# EtchController.net
KiCad netlist of a schematic drawn in EAGLE
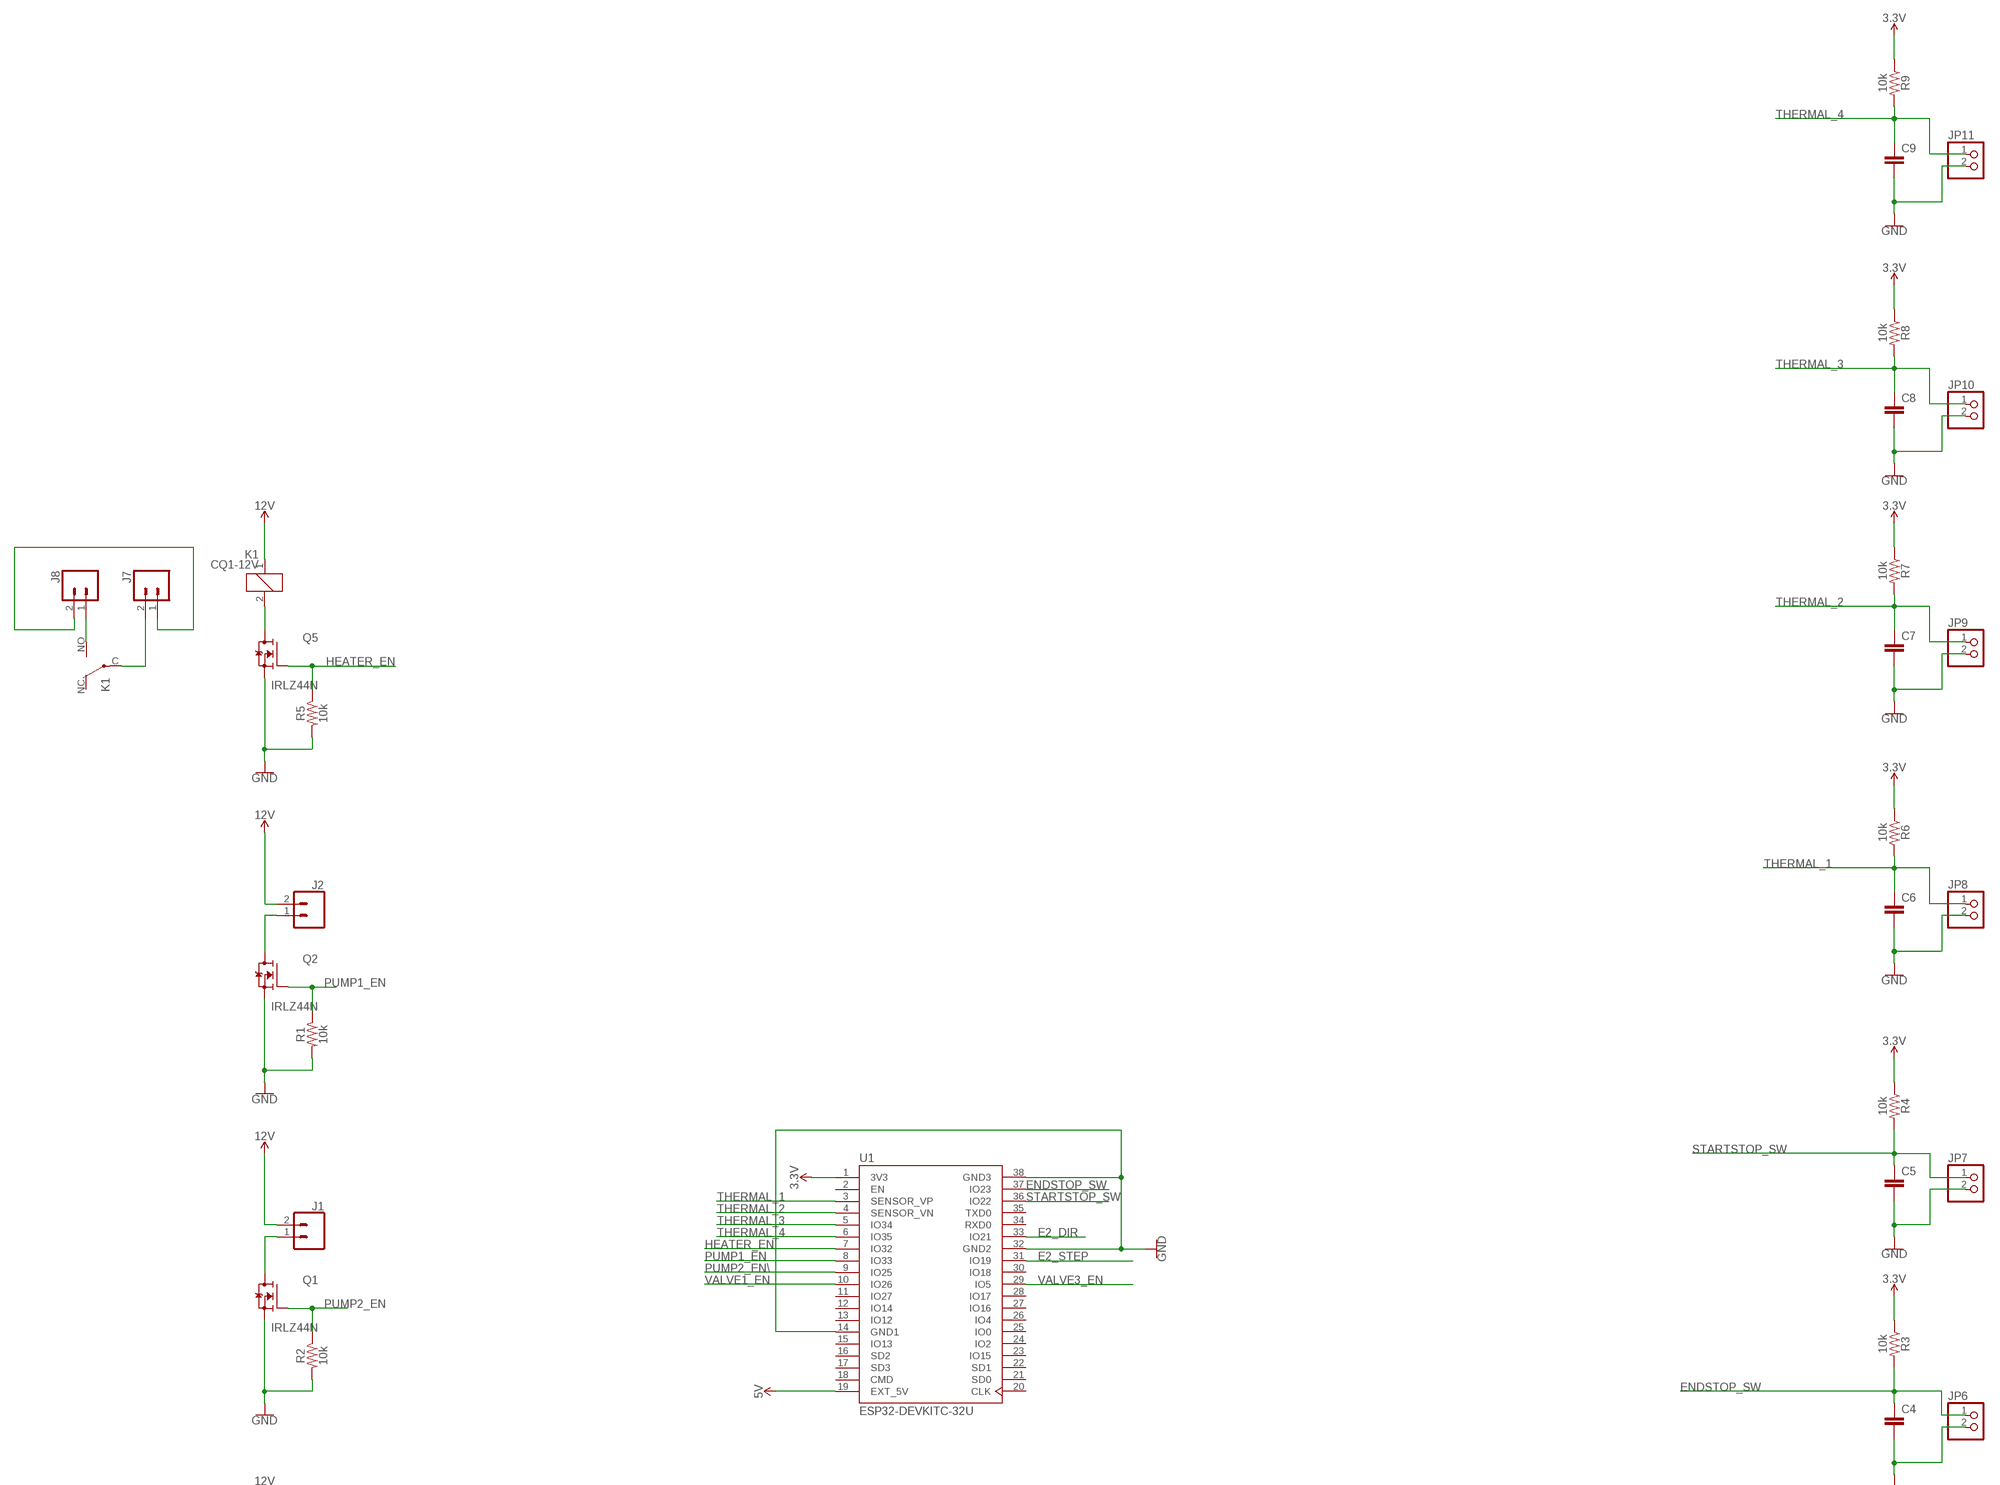
[diagram p0: schematic, sheet 1, part 1 of 2]
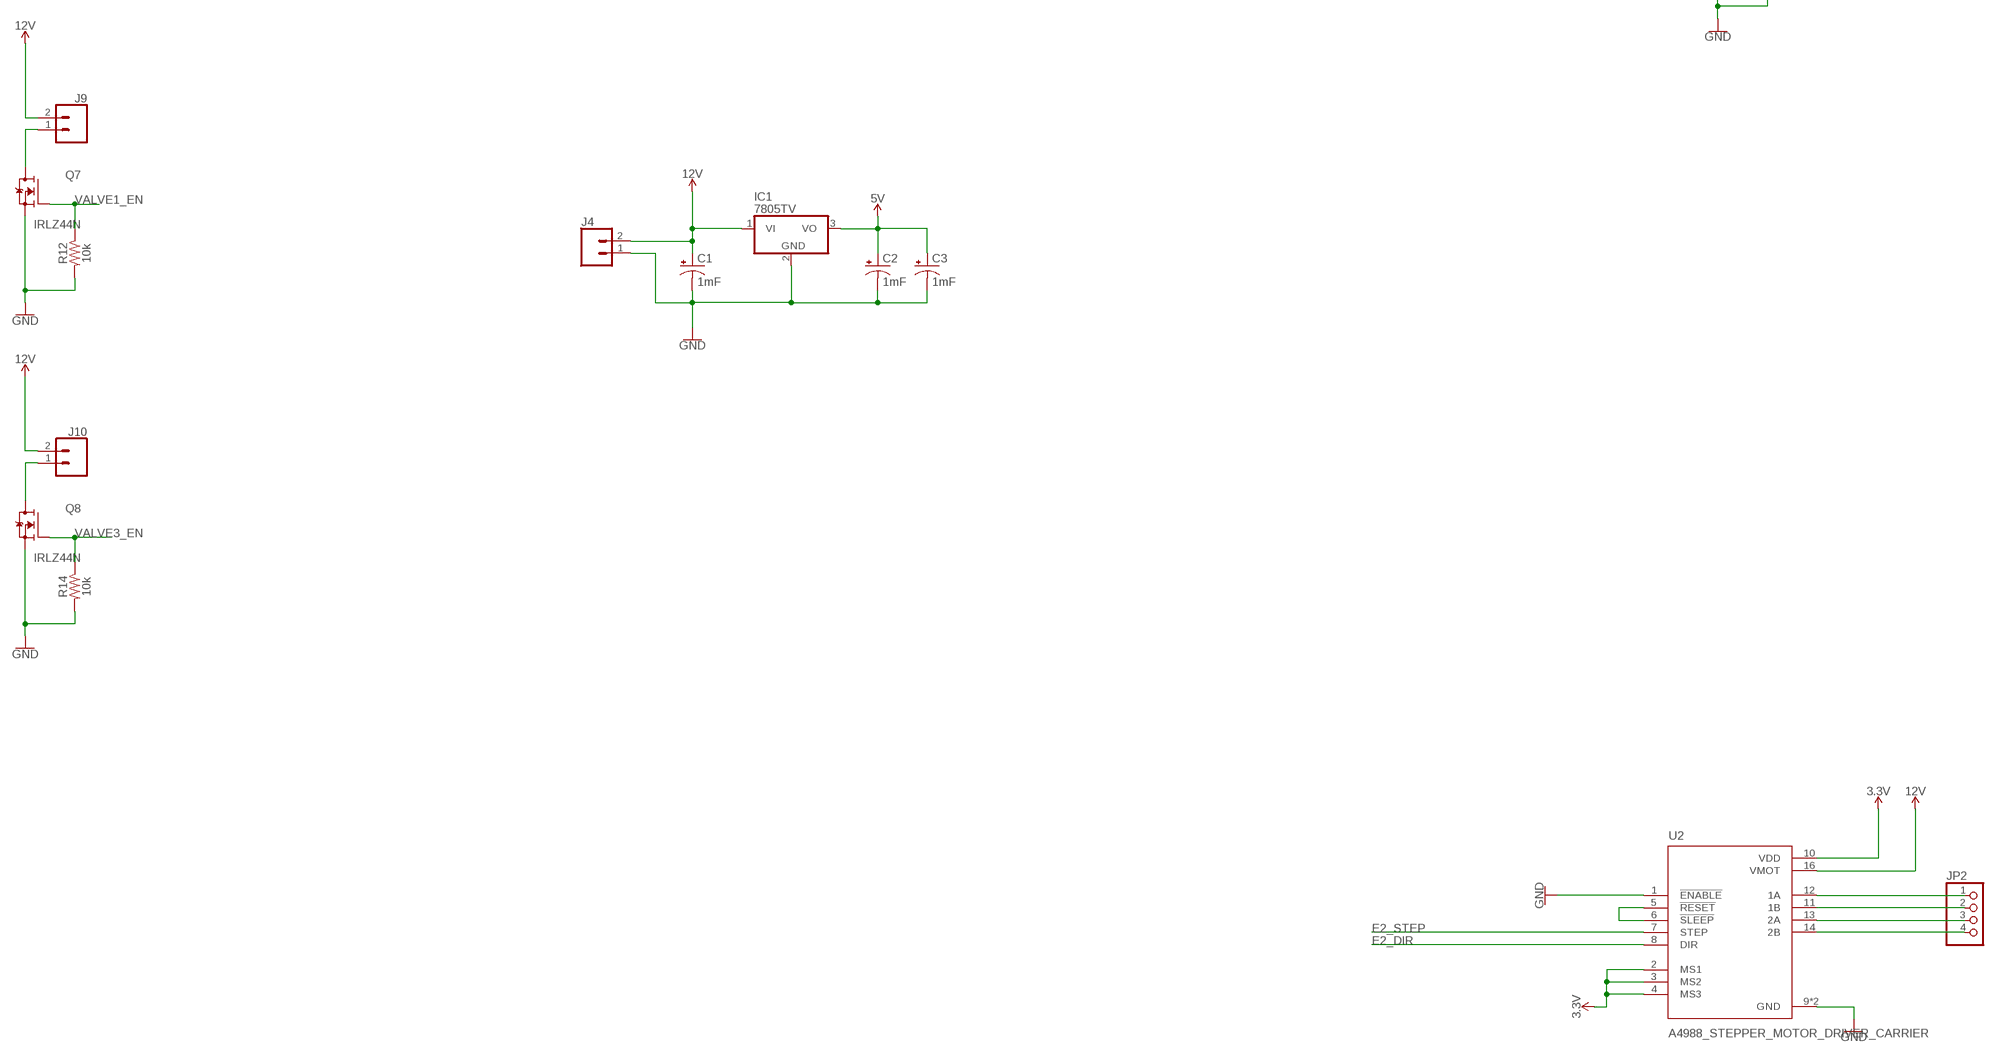
[diagram p1: schematic, sheet 1, part 2 of 2]

(export (version "E")
  (design (tool "Eeschema 10.0.6"))
  (components
    (comp (ref "C1")
      (value "1mF")
      (footprint "eagle-import:CPOL-RADIAL-5MM-10MM")
      (libsource (lib "eagle-import") (part "1000UF-RADIAL-5MM-25V-20%"))
    )
    (comp (ref "C2")
      (value "1mF")
      (footprint "eagle-import:CPOL-RADIAL-5MM-10MM")
      (libsource (lib "eagle-import") (part "1000UF-RADIAL-5MM-25V-20%"))
    )
    (comp (ref "C3")
      (value "1mF")
      (footprint "eagle-import:CPOL-RADIAL-5MM-10MM")
      (libsource (lib "eagle-import") (part "1000UF-RADIAL-5MM-25V-20%"))
    )
    (comp (ref "C4")
      (value "C2,5-3")
      (footprint "eagle-import:C2.5-3")
      (libsource (lib "eagle-import") (part "C2,5-3"))
    )
    (comp (ref "C5")
      (value "C2,5-3")
      (footprint "eagle-import:C2.5-3")
      (libsource (lib "eagle-import") (part "C2,5-3"))
    )
    (comp (ref "C6")
      (value "C2,5-3")
      (footprint "eagle-import:C2.5-3")
      (libsource (lib "eagle-import") (part "C2,5-3"))
    )
    (comp (ref "C7")
      (value "C2,5-3")
      (footprint "eagle-import:C2.5-3")
      (libsource (lib "eagle-import") (part "C2,5-3"))
    )
    (comp (ref "C8")
      (value "C2,5-3")
      (footprint "eagle-import:C2.5-3")
      (libsource (lib "eagle-import") (part "C2,5-3"))
    )
    (comp (ref "C9")
      (value "C2,5-3")
      (footprint "eagle-import:C2.5-3")
      (libsource (lib "eagle-import") (part "C2,5-3"))
    )
    (comp (ref "IC1")
      (value "7805TV")
      (footprint "eagle-import:TO220V")
      (libsource (lib "eagle-import") (part "78TV05"))
    )
    (comp (ref "J1")
      (value "CONN_023.5MM")
      (footprint "eagle-import:SCREWTERMINAL-3.5MM-2")
      (libsource (lib "eagle-import") (part "CONN_023.5MM"))
    )
    (comp (ref "J2")
      (value "CONN_023.5MM")
      (footprint "eagle-import:SCREWTERMINAL-3.5MM-2")
      (libsource (lib "eagle-import") (part "CONN_023.5MM"))
    )
    (comp (ref "J4")
      (value "CONN_023.5MM-NO_SILK")
      (footprint "eagle-import:SCREWTERMINAL-3.5MM-2-NS")
      (libsource (lib "eagle-import") (part "CONN_023.5MM-NO_SILK"))
    )
    (comp (ref "J7")
      (value "CONN_025MM")
      (footprint "eagle-import:SCREWTERMINAL-5MM-2")
      (libsource (lib "eagle-import") (part "CONN_025MM"))
    )
    (comp (ref "J8")
      (value "CONN_025MM")
      (footprint "eagle-import:SCREWTERMINAL-5MM-2")
      (libsource (lib "eagle-import") (part "CONN_025MM"))
    )
    (comp (ref "J9")
      (value "CONN_023.5MM")
      (footprint "eagle-import:SCREWTERMINAL-3.5MM-2")
      (libsource (lib "eagle-import") (part "CONN_023.5MM"))
    )
    (comp (ref "J10")
      (value "CONN_023.5MM")
      (footprint "eagle-import:SCREWTERMINAL-3.5MM-2")
      (libsource (lib "eagle-import") (part "CONN_023.5MM"))
    )
    (comp (ref "JP2")
      (value "PINHD-1X4")
      (footprint "eagle-import:1X04")
      (libsource (lib "eagle-import") (part "PINHD-1X4"))
    )
    (comp (ref "JP6")
      (value "PINHD-1X2")
      (footprint "eagle-import:1X02")
      (libsource (lib "eagle-import") (part "PINHD-1X2"))
    )
    (comp (ref "JP7")
      (value "PINHD-1X2")
      (footprint "eagle-import:1X02")
      (libsource (lib "eagle-import") (part "PINHD-1X2"))
    )
    (comp (ref "JP8")
      (value "PINHD-1X2")
      (footprint "eagle-import:1X02")
      (libsource (lib "eagle-import") (part "PINHD-1X2"))
    )
    (comp (ref "JP9")
      (value "PINHD-1X2")
      (footprint "eagle-import:1X02")
      (libsource (lib "eagle-import") (part "PINHD-1X2"))
    )
    (comp (ref "JP10")
      (value "PINHD-1X2")
      (footprint "eagle-import:1X02")
      (libsource (lib "eagle-import") (part "PINHD-1X2"))
    )
    (comp (ref "JP11")
      (value "PINHD-1X2")
      (footprint "eagle-import:1X02")
      (libsource (lib "eagle-import") (part "PINHD-1X2"))
    )
    (comp (ref "K1")
      (value "CQ1-12V")
      (footprint "eagle-import:CQ1")
      (libsource (lib "eagle-import") (part "CQ1-12V"))
    )
    (comp (ref "Q1")
      (value "IRLZ44N")
      (footprint "eagle-import:TO254P1054X469X1930-3")
      (fields (field (name "MF") "Infineon / IR"))
      (libsource (lib "eagle-import") (part "IRLZ44N"))
    )
    (comp (ref "Q2")
      (value "IRLZ44N")
      (footprint "eagle-import:TO254P1054X469X1930-3")
      (fields (field (name "MF") "Infineon / IR"))
      (libsource (lib "eagle-import") (part "IRLZ44N"))
    )
    (comp (ref "Q5")
      (value "IRLZ44N")
      (footprint "eagle-import:TO254P1054X469X1930-3")
      (fields (field (name "MF") "Infineon / IR"))
      (libsource (lib "eagle-import") (part "IRLZ44N"))
    )
    (comp (ref "Q7")
      (value "IRLZ44N")
      (footprint "eagle-import:TO254P1054X469X1930-3")
      (fields (field (name "MF") "Infineon / IR"))
      (libsource (lib "eagle-import") (part "IRLZ44N"))
    )
    (comp (ref "Q8")
      (value "IRLZ44N")
      (footprint "eagle-import:TO254P1054X469X1930-3")
      (fields (field (name "MF") "Infineon / IR"))
      (libsource (lib "eagle-import") (part "IRLZ44N"))
    )
    (comp (ref "R1")
      (value "10k")
      (footprint "eagle-import:AXIAL-0.1")
      (libsource (lib "eagle-import") (part "10KOHM-VERT-1/4W-1%"))
    )
    (comp (ref "R2")
      (value "10k")
      (footprint "eagle-import:AXIAL-0.1")
      (libsource (lib "eagle-import") (part "10KOHM-VERT-1/4W-1%"))
    )
    (comp (ref "R3")
      (value "10k")
      (footprint "eagle-import:AXIAL-0.1")
      (libsource (lib "eagle-import") (part "10KOHM-VERT-1/4W-1%"))
    )
    (comp (ref "R4")
      (value "10k")
      (footprint "eagle-import:AXIAL-0.1")
      (libsource (lib "eagle-import") (part "10KOHM-VERT-1/4W-1%"))
    )
    (comp (ref "R5")
      (value "10k")
      (footprint "eagle-import:AXIAL-0.1")
      (libsource (lib "eagle-import") (part "10KOHM-VERT-1/4W-1%"))
    )
    (comp (ref "R6")
      (value "10k")
      (footprint "eagle-import:AXIAL-0.1")
      (libsource (lib "eagle-import") (part "10KOHM-VERT-1/4W-1%"))
    )
    (comp (ref "R7")
      (value "10k")
      (footprint "eagle-import:AXIAL-0.1")
      (libsource (lib "eagle-import") (part "10KOHM-VERT-1/4W-1%"))
    )
    (comp (ref "R8")
      (value "10k")
      (footprint "eagle-import:AXIAL-0.1")
      (libsource (lib "eagle-import") (part "10KOHM-VERT-1/4W-1%"))
    )
    (comp (ref "R9")
      (value "10k")
      (footprint "eagle-import:AXIAL-0.1")
      (libsource (lib "eagle-import") (part "10KOHM-VERT-1/4W-1%"))
    )
    (comp (ref "R12")
      (value "10k")
      (footprint "eagle-import:AXIAL-0.1")
      (libsource (lib "eagle-import") (part "10KOHM-VERT-1/4W-1%"))
    )
    (comp (ref "R14")
      (value "10k")
      (footprint "eagle-import:AXIAL-0.1")
      (libsource (lib "eagle-import") (part "10KOHM-VERT-1/4W-1%"))
    )
    (comp (ref "U1")
      (value "ESP32-DEVKITC-32U")
      (footprint "eagle-import:MODULE_ESP32-DEVKITC-32U")
      (fields (field (name "MF") "Espressif Systems"))
      (libsource (lib "eagle-import") (part "ESP32-DEVKITC-32U"))
    )
    (comp (ref "U2")
      (value "A4988_STEPPER_MOTOR_DRIVER_CARRIER")
      (footprint "eagle-import:MODULE_A4988_STEPPER_MOTOR_DRIVER_CARRIER")
      (fields (field (name "MF") "Pololu") (field (name "MP") "A4988 STEPPER MOTOR DRIVER CARRIER"))
      (libsource (lib "eagle-import") (part "A4988_STEPPER_MOTOR_DRIVER_CARRIER"))
    )
  )
  (nets
    (net (code "1") (name "/E2_DIR") (class "Default")
      (node (ref "U1") (pin "33") (pinfunction "IO21_33") (pintype "bidirectional"))
      (node (ref "U2") (pin "8") (pinfunction "DIR_8") (pintype "input"))
    )
    (net (code "2") (name "/E2_STEP") (class "Default")
      (node (ref "U1") (pin "31") (pinfunction "IO19_31") (pintype "bidirectional"))
      (node (ref "U2") (pin "7") (pinfunction "STEP_7") (pintype "input"))
    )
    (net (code "3") (name "/ENDSTOP_SW") (class "Default")
      (node (ref "C4") (pin "1") (pinfunction "1_1") (pintype "passive"))
      (node (ref "JP6") (pin "1") (pinfunction "1_1") (pintype "passive"))
      (node (ref "R3") (pin "P$2") (pinfunction "2_P$2") (pintype "passive"))
      (node (ref "U1") (pin "37") (pinfunction "IO23_37") (pintype "bidirectional"))
    )
    (net (code "4") (name "/HEATER_EN") (class "Default")
      (node (ref "Q5") (pin "1") (pinfunction "G_1") (pintype "passive"))
      (node (ref "R5") (pin "P$1") (pinfunction "1_P$1") (pintype "passive"))
      (node (ref "U1") (pin "7") (pinfunction "IO32_7") (pintype "bidirectional"))
    )
    (net (code "5") (name "/PUMP1_EN") (class "Default")
      (node (ref "Q2") (pin "1") (pinfunction "G_1") (pintype "passive"))
      (node (ref "R1") (pin "P$1") (pinfunction "1_P$1") (pintype "passive"))
      (node (ref "U1") (pin "8") (pinfunction "IO33_8") (pintype "bidirectional"))
    )
    (net (code "6") (name "/PUMP2_EN") (class "Default")
      (node (ref "Q1") (pin "1") (pinfunction "G_1") (pintype "passive"))
      (node (ref "R2") (pin "P$1") (pinfunction "1_P$1") (pintype "passive"))
    )
    (net (code "7") (name "/PUMP2_EN\\") (class "Default")
      (node (ref "U1") (pin "9") (pinfunction "IO25_9") (pintype "bidirectional"))
    )
    (net (code "8") (name "/STARTSTOP_SW") (class "Default")
      (node (ref "C5") (pin "1") (pinfunction "1_1") (pintype "passive"))
      (node (ref "JP7") (pin "1") (pinfunction "1_1") (pintype "passive"))
      (node (ref "R4") (pin "P$2") (pinfunction "2_P$2") (pintype "passive"))
      (node (ref "U1") (pin "36") (pinfunction "IO22_36") (pintype "bidirectional"))
    )
    (net (code "9") (name "/THERMAL_1") (class "Default")
      (node (ref "C6") (pin "1") (pinfunction "1_1") (pintype "passive"))
      (node (ref "JP8") (pin "1") (pinfunction "1_1") (pintype "passive"))
      (node (ref "R6") (pin "P$2") (pinfunction "2_P$2") (pintype "passive"))
      (node (ref "U1") (pin "3") (pinfunction "SENSOR_VP_3") (pintype "input"))
    )
    (net (code "10") (name "/THERMAL_2") (class "Default")
      (node (ref "C7") (pin "1") (pinfunction "1_1") (pintype "passive"))
      (node (ref "JP9") (pin "1") (pinfunction "1_1") (pintype "passive"))
      (node (ref "R7") (pin "P$2") (pinfunction "2_P$2") (pintype "passive"))
      (node (ref "U1") (pin "4") (pinfunction "SENSOR_VN_4") (pintype "input"))
    )
    (net (code "11") (name "/THERMAL_3") (class "Default")
      (node (ref "C8") (pin "1") (pinfunction "1_1") (pintype "passive"))
      (node (ref "JP10") (pin "1") (pinfunction "1_1") (pintype "passive"))
      (node (ref "R8") (pin "P$2") (pinfunction "2_P$2") (pintype "passive"))
      (node (ref "U1") (pin "5") (pinfunction "IO34_5") (pintype "bidirectional"))
    )
    (net (code "12") (name "/THERMAL_4") (class "Default")
      (node (ref "C9") (pin "1") (pinfunction "1_1") (pintype "passive"))
      (node (ref "JP11") (pin "1") (pinfunction "1_1") (pintype "passive"))
      (node (ref "R9") (pin "P$2") (pinfunction "2_P$2") (pintype "passive"))
      (node (ref "U1") (pin "6") (pinfunction "IO35_6") (pintype "bidirectional"))
    )
    (net (code "13") (name "/VALVE1_EN") (class "Default")
      (node (ref "Q7") (pin "1") (pinfunction "G_1") (pintype "passive"))
      (node (ref "R12") (pin "P$1") (pinfunction "1_P$1") (pintype "passive"))
      (node (ref "U1") (pin "10") (pinfunction "IO26_10") (pintype "bidirectional"))
    )
    (net (code "14") (name "/VALVE3_EN") (class "Default")
      (node (ref "Q8") (pin "1") (pinfunction "G_1") (pintype "passive"))
      (node (ref "R14") (pin "P$1") (pinfunction "1_P$1") (pintype "passive"))
      (node (ref "U1") (pin "29") (pinfunction "IO5_29") (pintype "bidirectional"))
    )
    (net (code "15") (name "3.3V") (class "Default")
      (node (ref "R3") (pin "P$1") (pinfunction "1_P$1") (pintype "passive"))
      (node (ref "R4") (pin "P$1") (pinfunction "1_P$1") (pintype "passive"))
      (node (ref "R6") (pin "P$1") (pinfunction "1_P$1") (pintype "passive"))
      (node (ref "R7") (pin "P$1") (pinfunction "1_P$1") (pintype "passive"))
      (node (ref "R8") (pin "P$1") (pinfunction "1_P$1") (pintype "passive"))
      (node (ref "R9") (pin "P$1") (pinfunction "1_P$1") (pintype "passive"))
      (node (ref "U1") (pin "1") (pinfunction "3V3_1") (pintype "power_in"))
      (node (ref "U2") (pin "10") (pinfunction "VDD_10") (pintype "power_in"))
      (node (ref "U2") (pin "2") (pinfunction "MS1_2") (pintype "input"))
      (node (ref "U2") (pin "3") (pinfunction "MS2_3") (pintype "input"))
      (node (ref "U2") (pin "4") (pinfunction "MS3_4") (pintype "input"))
    )
    (net (code "16") (name "5V") (class "Default")
      (node (ref "C2") (pin "+") (pinfunction "+_+") (pintype "passive"))
      (node (ref "C3") (pin "+") (pinfunction "+_+") (pintype "passive"))
      (node (ref "IC1") (pin "3") (pinfunction "VO_3") (pintype "passive"))
      (node (ref "U1") (pin "19") (pinfunction "EXT_5V_19") (pintype "power_in"))
    )
    (net (code "17") (name "12V") (class "Default")
      (node (ref "C1") (pin "+") (pinfunction "+_+") (pintype "passive"))
      (node (ref "IC1") (pin "1") (pinfunction "VI_1") (pintype "input"))
      (node (ref "J1") (pin "2") (pinfunction "2_2") (pintype "passive"))
      (node (ref "J10") (pin "2") (pinfunction "2_2") (pintype "passive"))
      (node (ref "J2") (pin "2") (pinfunction "2_2") (pintype "passive"))
      (node (ref "J4") (pin "2") (pinfunction "2_2") (pintype "passive"))
      (node (ref "J9") (pin "2") (pinfunction "2_2") (pintype "passive"))
      (node (ref "K1") (pin "1") (pinfunction "1_1") (pintype "passive"))
      (node (ref "U2") (pin "16") (pinfunction "VMOT_16") (pintype "power_in"))
    )
    (net (code "18") (name "GND") (class "Default")
      (node (ref "C1") (pin "-") (pinfunction "-_-") (pintype "passive"))
      (node (ref "C2") (pin "-") (pinfunction "-_-") (pintype "passive"))
      (node (ref "C3") (pin "-") (pinfunction "-_-") (pintype "passive"))
      (node (ref "C4") (pin "2") (pinfunction "2_2") (pintype "passive"))
      (node (ref "C5") (pin "2") (pinfunction "2_2") (pintype "passive"))
      (node (ref "C6") (pin "2") (pinfunction "2_2") (pintype "passive"))
      (node (ref "C7") (pin "2") (pinfunction "2_2") (pintype "passive"))
      (node (ref "C8") (pin "2") (pinfunction "2_2") (pintype "passive"))
      (node (ref "C9") (pin "2") (pinfunction "2_2") (pintype "passive"))
      (node (ref "IC1") (pin "2") (pinfunction "GND_2") (pintype "passive"))
      (node (ref "J4") (pin "1") (pinfunction "1_1") (pintype "passive"))
      (node (ref "JP10") (pin "2") (pinfunction "2_2") (pintype "passive"))
      (node (ref "JP11") (pin "2") (pinfunction "2_2") (pintype "passive"))
      (node (ref "JP6") (pin "2") (pinfunction "2_2") (pintype "passive"))
      (node (ref "JP7") (pin "2") (pinfunction "2_2") (pintype "passive"))
      (node (ref "JP8") (pin "2") (pinfunction "2_2") (pintype "passive"))
      (node (ref "JP9") (pin "2") (pinfunction "2_2") (pintype "passive"))
      (node (ref "Q1") (pin "3") (pinfunction "S_3") (pintype "passive"))
      (node (ref "Q2") (pin "3") (pinfunction "S_3") (pintype "passive"))
      (node (ref "Q5") (pin "3") (pinfunction "S_3") (pintype "passive"))
      (node (ref "Q7") (pin "3") (pinfunction "S_3") (pintype "passive"))
      (node (ref "Q8") (pin "3") (pinfunction "S_3") (pintype "passive"))
      (node (ref "R1") (pin "P$2") (pinfunction "2_P$2") (pintype "passive"))
      (node (ref "R12") (pin "P$2") (pinfunction "2_P$2") (pintype "passive"))
      (node (ref "R14") (pin "P$2") (pinfunction "2_P$2") (pintype "passive"))
      (node (ref "R2") (pin "P$2") (pinfunction "2_P$2") (pintype "passive"))
      (node (ref "R5") (pin "P$2") (pinfunction "2_P$2") (pintype "passive"))
      (node (ref "U1") (pin "14") (pinfunction "GND1_14") (pintype "power_in"))
      (node (ref "U1") (pin "32") (pinfunction "GND2_32") (pintype "power_in"))
      (node (ref "U1") (pin "38") (pinfunction "GND3_38") (pintype "power_in"))
      (node (ref "U2") (pin "1") (pinfunction "~{ENABLE}_1") (pintype "input"))
      (node (ref "U2") (pin "15") (pinfunction "GND_15") (pintype "power_in"))
      (node (ref "U2") (pin "9") (pinfunction "GND_9") (pintype "power_in"))
    )
    (net (code "19") (name "Net-(J7-Pad1)") (class "Default")
      (node (ref "J7") (pin "1") (pinfunction "1_1") (pintype "passive"))
      (node (ref "J8") (pin "2") (pinfunction "2_2") (pintype "passive"))
    )
    (net (code "20") (name "Net-(K1B-P)") (class "Default")
      (node (ref "J7") (pin "2") (pinfunction "2_2") (pintype "passive"))
      (node (ref "K1") (pin "C") (pinfunction "P_C") (pintype "passive"))
    )
    (net (code "21") (name "Net-(K1B-S)") (class "Default")
      (node (ref "J8") (pin "1") (pinfunction "1_1") (pintype "passive"))
      (node (ref "K1") (pin "NO") (pinfunction "S_NO") (pintype "passive"))
    )
    (net (code "22") (name "Net-(Q1-D)") (class "Default")
      (node (ref "J1") (pin "1") (pinfunction "1_1") (pintype "passive"))
      (node (ref "Q1") (pin "2") (pinfunction "D_2") (pintype "passive"))
    )
    (net (code "23") (name "Net-(Q2-D)") (class "Default")
      (node (ref "J2") (pin "1") (pinfunction "1_1") (pintype "passive"))
      (node (ref "Q2") (pin "2") (pinfunction "D_2") (pintype "passive"))
    )
    (net (code "24") (name "Net-(Q5-D)") (class "Default")
      (node (ref "K1") (pin "2") (pinfunction "2_2") (pintype "passive"))
      (node (ref "Q5") (pin "2") (pinfunction "D_2") (pintype "passive"))
    )
    (net (code "25") (name "Net-(Q7-D)") (class "Default")
      (node (ref "J9") (pin "1") (pinfunction "1_1") (pintype "passive"))
      (node (ref "Q7") (pin "2") (pinfunction "D_2") (pintype "passive"))
    )
    (net (code "26") (name "Net-(Q8-D)") (class "Default")
      (node (ref "J10") (pin "1") (pinfunction "1_1") (pintype "passive"))
      (node (ref "Q8") (pin "2") (pinfunction "D_2") (pintype "passive"))
    )
    (net (code "27") (name "Net-(U2-1A)") (class "Default")
      (node (ref "JP2") (pin "1") (pinfunction "1_1") (pintype "passive"))
      (node (ref "U2") (pin "12") (pinfunction "1A_12") (pintype "output"))
    )
    (net (code "28") (name "Net-(U2-1B)") (class "Default")
      (node (ref "JP2") (pin "2") (pinfunction "2_2") (pintype "passive"))
      (node (ref "U2") (pin "11") (pinfunction "1B_11") (pintype "output"))
    )
    (net (code "29") (name "Net-(U2-2A)") (class "Default")
      (node (ref "JP2") (pin "3") (pinfunction "3_3") (pintype "passive"))
      (node (ref "U2") (pin "13") (pinfunction "2A_13") (pintype "output"))
    )
    (net (code "30") (name "Net-(U2-2B)") (class "Default")
      (node (ref "JP2") (pin "4") (pinfunction "4_4") (pintype "passive"))
      (node (ref "U2") (pin "14") (pinfunction "2B_14") (pintype "output"))
    )
    (net (code "31") (name "Net-(U2-~{RESET})") (class "Default")
      (node (ref "U2") (pin "5") (pinfunction "~{RESET}_5") (pintype "input"))
      (node (ref "U2") (pin "6") (pinfunction "~{SLEEP}_6") (pintype "input"))
    )
    (net (code "32") (name "unconnected-(K1B-O-PadNC)") (class "Default")
      (node (ref "K1") (pin "NC") (pinfunction "O_NC") (pintype "passive"))
    )
    (net (code "33") (name "unconnected-(U1-CLK-Pad20)") (class "Default")
      (node (ref "U1") (pin "20") (pinfunction "CLK_20") (pintype "input"))
    )
    (net (code "34") (name "unconnected-(U1-CMD-Pad18)") (class "Default")
      (node (ref "U1") (pin "18") (pinfunction "CMD_18") (pintype "bidirectional"))
    )
    (net (code "35") (name "unconnected-(U1-EN-Pad2)") (class "Default")
      (node (ref "U1") (pin "2") (pinfunction "EN_2") (pintype "input"))
    )
    (net (code "36") (name "unconnected-(U1-IO0-Pad25)") (class "Default")
      (node (ref "U1") (pin "25") (pinfunction "IO0_25") (pintype "bidirectional"))
    )
    (net (code "37") (name "unconnected-(U1-IO2-Pad24)") (class "Default")
      (node (ref "U1") (pin "24") (pinfunction "IO2_24") (pintype "bidirectional"))
    )
    (net (code "38") (name "unconnected-(U1-IO4-Pad26)") (class "Default")
      (node (ref "U1") (pin "26") (pinfunction "IO4_26") (pintype "bidirectional"))
    )
    (net (code "39") (name "unconnected-(U1-IO12-Pad13)") (class "Default")
      (node (ref "U1") (pin "13") (pinfunction "IO12_13") (pintype "bidirectional"))
    )
    (net (code "40") (name "unconnected-(U1-IO13-Pad15)") (class "Default")
      (node (ref "U1") (pin "15") (pinfunction "IO13_15") (pintype "bidirectional"))
    )
    (net (code "41") (name "unconnected-(U1-IO14-Pad12)") (class "Default")
      (node (ref "U1") (pin "12") (pinfunction "IO14_12") (pintype "bidirectional"))
    )
    (net (code "42") (name "unconnected-(U1-IO15-Pad23)") (class "Default")
      (node (ref "U1") (pin "23") (pinfunction "IO15_23") (pintype "bidirectional"))
    )
    (net (code "43") (name "unconnected-(U1-IO16-Pad27)") (class "Default")
      (node (ref "U1") (pin "27") (pinfunction "IO16_27") (pintype "bidirectional"))
    )
    (net (code "44") (name "unconnected-(U1-IO17-Pad28)") (class "Default")
      (node (ref "U1") (pin "28") (pinfunction "IO17_28") (pintype "bidirectional"))
    )
    (net (code "45") (name "unconnected-(U1-IO18-Pad30)") (class "Default")
      (node (ref "U1") (pin "30") (pinfunction "IO18_30") (pintype "bidirectional"))
    )
    (net (code "46") (name "unconnected-(U1-IO27-Pad11)") (class "Default")
      (node (ref "U1") (pin "11") (pinfunction "IO27_11") (pintype "bidirectional"))
    )
    (net (code "47") (name "unconnected-(U1-RXD0-Pad34)") (class "Default")
      (node (ref "U1") (pin "34") (pinfunction "RXD0_34") (pintype "input"))
    )
    (net (code "48") (name "unconnected-(U1-SD0-Pad21)") (class "Default")
      (node (ref "U1") (pin "21") (pinfunction "SD0_21") (pintype "bidirectional"))
    )
    (net (code "49") (name "unconnected-(U1-SD1-Pad22)") (class "Default")
      (node (ref "U1") (pin "22") (pinfunction "SD1_22") (pintype "bidirectional"))
    )
    (net (code "50") (name "unconnected-(U1-SD2-Pad16)") (class "Default")
      (node (ref "U1") (pin "16") (pinfunction "SD2_16") (pintype "bidirectional"))
    )
    (net (code "51") (name "unconnected-(U1-SD3-Pad17)") (class "Default")
      (node (ref "U1") (pin "17") (pinfunction "SD3_17") (pintype "bidirectional"))
    )
    (net (code "52") (name "unconnected-(U1-TXD0-Pad35)") (class "Default")
      (node (ref "U1") (pin "35") (pinfunction "TXD0_35") (pintype "output"))
    )
  )
)
